# relay_and_led_RGB.net
KiCad netlist of a schematic drawn in Altium Designer
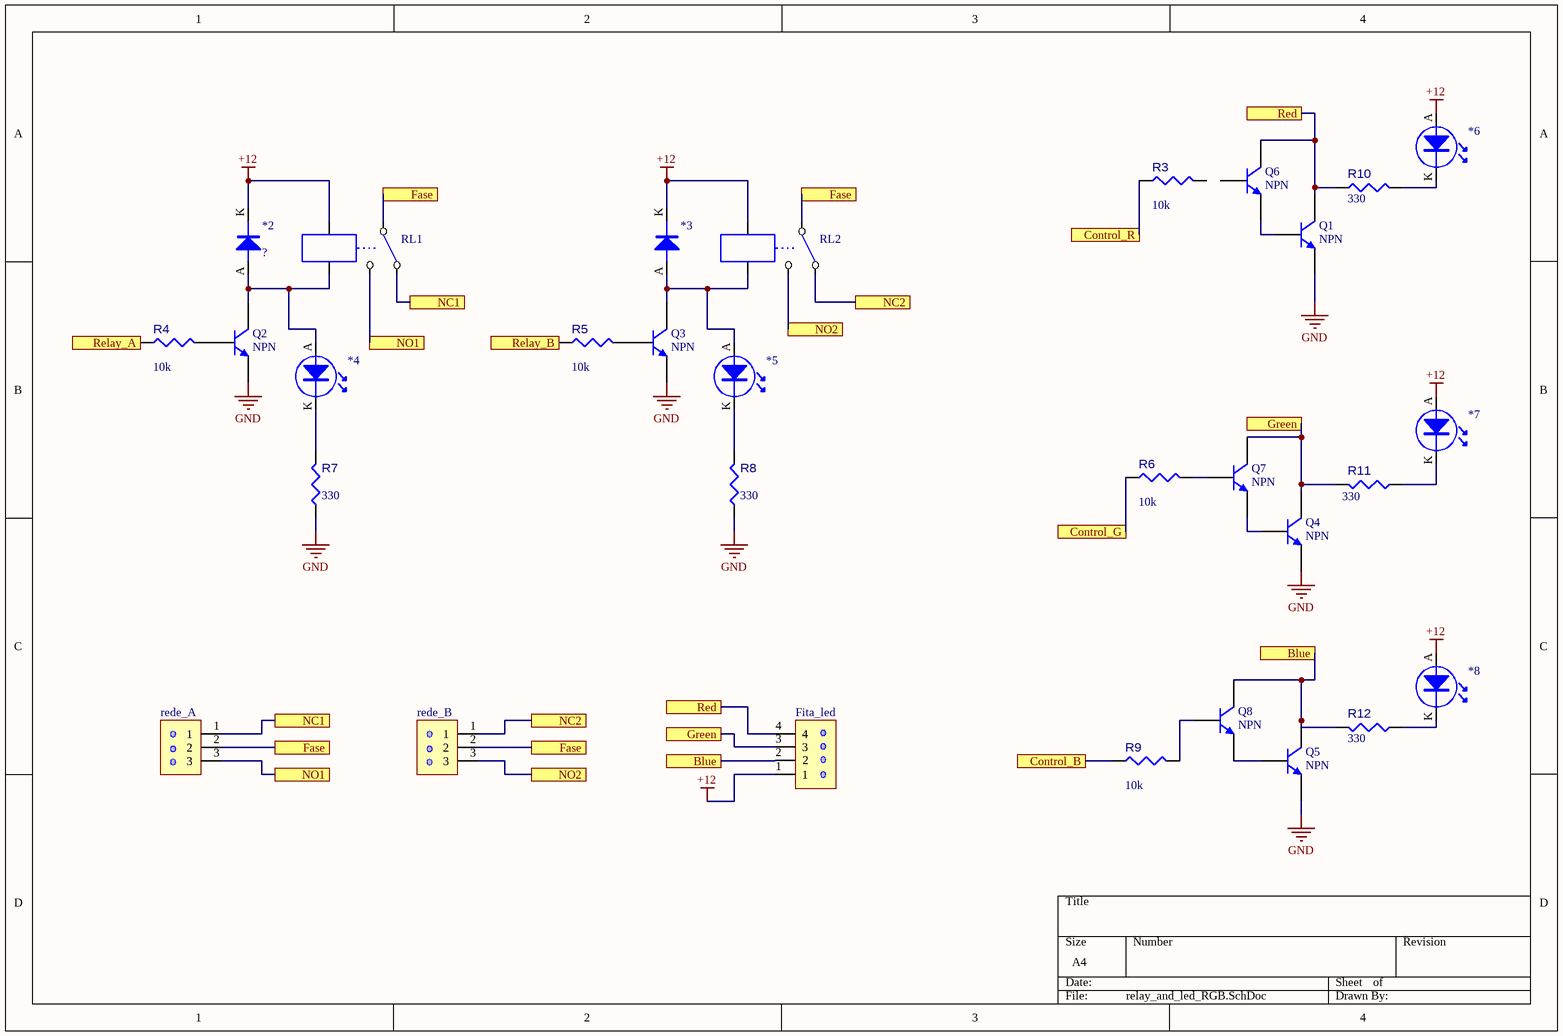
[diagram p0: relay_and_led_RGB.SchDoc]

(export (version "E")
  (design (tool "Eeschema 10.0.6"))
  (components
    (comp (ref "*2")
      (value "?")
      (footprint "DIO_PTH_DO41")
      (fields (field (name "Comment") "DIO_PTH_1N4007"))
      (libsource (lib "i9Library_Altium") (part "DIO_PTH_1N4007"))
    )
    (comp (ref "*3")
      (value "DIO_PTH_1N4007")
      (footprint "DIO_PTH_DO41")
      (libsource (lib "i9Library_Altium") (part "DIO_PTH_1N4007"))
    )
    (comp (ref "*4")
      (value "LED_AXIAL_5MM")
      (footprint "HEADER_1X2")
      (libsource (lib "i9Library_Altium") (part "LED_AXIAL_5MM"))
    )
    (comp (ref "*5")
      (value "LED_AXIAL_5MM")
      (footprint "HEADER_1X2")
      (libsource (lib "i9Library_Altium") (part "LED_AXIAL_5MM"))
    )
    (comp (ref "*6")
      (value "LED_AXIAL_5MM")
      (footprint "HEADER_1X2")
      (libsource (lib "i9Library_Altium") (part "LED_AXIAL_5MM"))
    )
    (comp (ref "*7")
      (value "LED_AXIAL_5MM")
      (footprint "HEADER_1X2")
      (libsource (lib "i9Library_Altium") (part "LED_AXIAL_5MM"))
    )
    (comp (ref "*8")
      (value "LED_AXIAL_5MM")
      (footprint "HEADER_1X2")
      (libsource (lib "i9Library_Altium") (part "LED_AXIAL_5MM"))
    )
    (comp (ref "Fita_led")
      (value "CN_KK_4")
      (footprint "CN_KK_4_5045-4")
      (description "KK_4")
      (libsource (lib "i9Library_Altium") (part "CN_KK_4"))
    )
    (comp (ref "Q1")
      (value "NPN")
      (footprint "HEADER_1X3")
      (description "NPN Bipolar Transistor")
      (fields (field (name "PUBLISHER") "Altium Limited"))
      (libsource (lib "Miscellaneous Devices") (part "NPN"))
    )
    (comp (ref "Q2")
      (value "NPN")
      (footprint "HEADER_1X3")
      (description "NPN Bipolar Transistor")
      (fields (field (name "PUBLISHER") "Altium Limited"))
      (libsource (lib "Miscellaneous Devices") (part "NPN"))
    )
    (comp (ref "Q3")
      (value "NPN")
      (footprint "HEADER_1X3")
      (description "NPN Bipolar Transistor")
      (fields (field (name "PUBLISHER") "Altium Limited"))
      (libsource (lib "Miscellaneous Devices") (part "NPN"))
    )
    (comp (ref "Q4")
      (value "NPN")
      (footprint "HEADER_1X3")
      (description "NPN Bipolar Transistor")
      (fields (field (name "PUBLISHER") "Altium Limited"))
      (libsource (lib "Miscellaneous Devices") (part "NPN"))
    )
    (comp (ref "Q5")
      (value "NPN")
      (footprint "HEADER_1X3")
      (description "NPN Bipolar Transistor")
      (fields (field (name "PUBLISHER") "Altium Limited"))
      (libsource (lib "Miscellaneous Devices") (part "NPN"))
    )
    (comp (ref "Q6")
      (value "NPN")
      (footprint "HEADER_1X3")
      (description "NPN Bipolar Transistor")
      (fields (field (name "PUBLISHER") "Altium Limited"))
      (libsource (lib "Miscellaneous Devices") (part "NPN"))
    )
    (comp (ref "Q7")
      (value "NPN")
      (footprint "HEADER_1X3")
      (description "NPN Bipolar Transistor")
      (fields (field (name "PUBLISHER") "Altium Limited"))
      (libsource (lib "Miscellaneous Devices") (part "NPN"))
    )
    (comp (ref "Q8")
      (value "NPN")
      (footprint "HEADER_1X3")
      (description "NPN Bipolar Transistor")
      (fields (field (name "PUBLISHER") "Altium Limited"))
      (libsource (lib "Miscellaneous Devices") (part "NPN"))
    )
    (comp (ref "R3")
      (value "10k")
      (footprint "RES_PTH_7.62MM")
      (description "Pin Through Hole Resistor 7.62mm")
      (libsource (lib "i9Library_Altium") (part "RES_PTH_7.62MM"))
    )
    (comp (ref "R4")
      (value "10k")
      (footprint "RES_PTH_7.62MM")
      (description "Pin Through Hole Resistor 7.62mm")
      (libsource (lib "i9Library_Altium") (part "RES_PTH_7.62MM"))
    )
    (comp (ref "R5")
      (value "10k")
      (footprint "RES_PTH_7.62MM")
      (description "Pin Through Hole Resistor 7.62mm")
      (libsource (lib "i9Library_Altium") (part "RES_PTH_7.62MM"))
    )
    (comp (ref "R6")
      (value "10k")
      (footprint "RES_PTH_7.62MM")
      (description "Pin Through Hole Resistor 7.62mm")
      (libsource (lib "i9Library_Altium") (part "RES_PTH_7.62MM"))
    )
    (comp (ref "R7")
      (value "330")
      (footprint "RES_PTH_7.62MM")
      (description "Pin Through Hole Resistor 7.62mm")
      (libsource (lib "i9Library_Altium") (part "RES_PTH_7.62MM"))
    )
    (comp (ref "R8")
      (value "330")
      (footprint "RES_PTH_7.62MM")
      (description "Pin Through Hole Resistor 7.62mm")
      (libsource (lib "i9Library_Altium") (part "RES_PTH_7.62MM"))
    )
    (comp (ref "R9")
      (value "10k")
      (footprint "RES_PTH_7.62MM")
      (description "Pin Through Hole Resistor 7.62mm")
      (libsource (lib "i9Library_Altium") (part "RES_PTH_7.62MM"))
    )
    (comp (ref "R10")
      (value "330")
      (footprint "RES_PTH_7.62MM")
      (description "Pin Through Hole Resistor 7.62mm")
      (libsource (lib "i9Library_Altium") (part "RES_PTH_7.62MM"))
    )
    (comp (ref "R11")
      (value "330")
      (footprint "RES_PTH_7.62MM")
      (description "Pin Through Hole Resistor 7.62mm")
      (libsource (lib "i9Library_Altium") (part "RES_PTH_7.62MM"))
    )
    (comp (ref "R12")
      (value "330")
      (footprint "RES_PTH_7.62MM")
      (description "Pin Through Hole Resistor 7.62mm")
      (libsource (lib "i9Library_Altium") (part "RES_PTH_7.62MM"))
    )
    (comp (ref "rede_A")
      (value "?")
      (footprint "CN_KRE_3")
      (description "MKDS_3")
      (libsource (lib "i9Library_Altium") (part "CN_MKDS_3"))
    )
    (comp (ref "rede_B")
      (value "?")
      (footprint "CN_KRE_3")
      (description "MKDS_3")
      (libsource (lib "i9Library_Altium") (part "CN_MKDS_3"))
    )
    (comp (ref "RL1")
      (value "RELEICR5551")
      (footprint "DIV_RELE_5551")
      (libsource (lib "i9Library_Altium") (part "RELEICR5551"))
    )
    (comp (ref "RL2")
      (value "RELEICR5551")
      (footprint "DIV_RELE_5551")
      (libsource (lib "i9Library_Altium") (part "RELEICR5551"))
    )
  )
  (nets
    (net (code "1") (name "+12") (class "Default")
      (node (ref "*2") (pin "K") (pintype "passive"))
      (node (ref "*3") (pin "K") (pintype "passive"))
      (node (ref "*6") (pin "A") (pintype "passive"))
      (node (ref "*7") (pin "A") (pintype "passive"))
      (node (ref "*8") (pin "A") (pintype "passive"))
      (node (ref "Fita_led") (pin "1") (pinfunction "1_1") (pintype "passive"))
      (node (ref "RL1") (pin "4") (pintype "passive"))
      (node (ref "RL2") (pin "4") (pintype "passive"))
    )
    (net (code "2") (name "/Blue") (class "Default")
      (node (ref "Fita_led") (pin "2") (pinfunction "2_2") (pintype "passive"))
      (node (ref "Q5") (pin "1") (pinfunction "C_1") (pintype "passive"))
      (node (ref "Q8") (pin "1") (pinfunction "C_1") (pintype "passive"))
      (node (ref "R12") (pin "2") (pinfunction "2_2") (pintype "passive"))
    )
    (net (code "3") (name "/Control_B") (class "Default")
      (node (ref "R9") (pin "1") (pinfunction "1_1") (pintype "passive"))
    )
    (net (code "4") (name "/Control_G") (class "Default")
      (node (ref "R6") (pin "1") (pinfunction "1_1") (pintype "passive"))
    )
    (net (code "5") (name "/Control_R") (class "Default")
      (node (ref "R3") (pin "1") (pinfunction "1_1") (pintype "passive"))
    )
    (net (code "6") (name "/Fase") (class "Default")
      (node (ref "RL1") (pin "1") (pintype "passive"))
      (node (ref "RL2") (pin "1") (pintype "passive"))
      (node (ref "rede_A") (pin "2") (pinfunction "2_2") (pintype "passive"))
      (node (ref "rede_B") (pin "2") (pinfunction "2_2") (pintype "passive"))
    )
    (net (code "7") (name "/Green") (class "Default")
      (node (ref "Fita_led") (pin "3") (pinfunction "3_3") (pintype "passive"))
      (node (ref "Q4") (pin "1") (pinfunction "C_1") (pintype "passive"))
      (node (ref "Q7") (pin "1") (pinfunction "C_1") (pintype "passive"))
      (node (ref "R11") (pin "2") (pinfunction "2_2") (pintype "passive"))
    )
    (net (code "8") (name "/NC1") (class "Default")
      (node (ref "RL1") (pin "2") (pintype "passive"))
      (node (ref "rede_A") (pin "1") (pinfunction "1_1") (pintype "passive"))
    )
    (net (code "9") (name "/NC2") (class "Default")
      (node (ref "RL2") (pin "2") (pintype "passive"))
      (node (ref "rede_B") (pin "1") (pinfunction "1_1") (pintype "passive"))
    )
    (net (code "10") (name "/NO1") (class "Default")
      (node (ref "RL1") (pin "3") (pintype "passive"))
      (node (ref "rede_A") (pin "3") (pinfunction "3_3") (pintype "passive"))
    )
    (net (code "11") (name "/NO2") (class "Default")
      (node (ref "RL2") (pin "3") (pintype "passive"))
      (node (ref "rede_B") (pin "3") (pinfunction "3_3") (pintype "passive"))
    )
    (net (code "12") (name "/Red") (class "Default")
      (node (ref "Fita_led") (pin "4") (pinfunction "4_4") (pintype "passive"))
      (node (ref "Q1") (pin "1") (pinfunction "C_1") (pintype "passive"))
      (node (ref "Q6") (pin "1") (pinfunction "C_1") (pintype "passive"))
      (node (ref "R10") (pin "1") (pinfunction "1_1") (pintype "passive"))
    )
    (net (code "13") (name "/Relay_A") (class "Default")
      (node (ref "R4") (pin "1") (pinfunction "1_1") (pintype "passive"))
    )
    (net (code "14") (name "/Relay_B") (class "Default")
      (node (ref "R5") (pin "1") (pinfunction "1_1") (pintype "passive"))
    )
    (net (code "15") (name "GND") (class "Default")
      (node (ref "Q1") (pin "3") (pinfunction "E_3") (pintype "passive"))
      (node (ref "Q2") (pin "3") (pinfunction "E_3") (pintype "passive"))
      (node (ref "Q3") (pin "3") (pinfunction "E_3") (pintype "passive"))
      (node (ref "Q4") (pin "3") (pinfunction "E_3") (pintype "passive"))
      (node (ref "Q5") (pin "3") (pinfunction "E_3") (pintype "passive"))
      (node (ref "R7") (pin "1") (pinfunction "1_1") (pintype "passive"))
      (node (ref "R8") (pin "1") (pinfunction "1_1") (pintype "passive"))
    )
    (net (code "16") (name "Net-(*4-PadK)") (class "Default")
      (node (ref "*4") (pin "K") (pintype "passive"))
      (node (ref "R7") (pin "2") (pinfunction "2_2") (pintype "passive"))
    )
    (net (code "17") (name "Net-(*5-PadK)") (class "Default")
      (node (ref "*5") (pin "K") (pintype "passive"))
      (node (ref "R8") (pin "2") (pinfunction "2_2") (pintype "passive"))
    )
    (net (code "18") (name "Net-(*6-PadK)") (class "Default")
      (node (ref "*6") (pin "K") (pintype "passive"))
      (node (ref "R10") (pin "2") (pinfunction "2_2") (pintype "passive"))
    )
    (net (code "19") (name "Net-(*7-PadK)") (class "Default")
      (node (ref "*7") (pin "K") (pintype "passive"))
      (node (ref "R11") (pin "1") (pinfunction "1_1") (pintype "passive"))
    )
    (net (code "20") (name "Net-(*8-PadK)") (class "Default")
      (node (ref "*8") (pin "K") (pintype "passive"))
      (node (ref "R12") (pin "1") (pinfunction "1_1") (pintype "passive"))
    )
    (net (code "21") (name "Net-(Q1-B)") (class "Default")
      (node (ref "Q1") (pin "2") (pinfunction "B_2") (pintype "passive"))
      (node (ref "Q6") (pin "3") (pinfunction "E_3") (pintype "passive"))
    )
    (net (code "22") (name "Net-(Q2-B)") (class "Default")
      (node (ref "Q2") (pin "2") (pinfunction "B_2") (pintype "passive"))
      (node (ref "R4") (pin "2") (pinfunction "2_2") (pintype "passive"))
    )
    (net (code "23") (name "Net-(Q2-C)") (class "Default")
      (node (ref "*2") (pin "A") (pintype "passive"))
      (node (ref "*4") (pin "A") (pintype "passive"))
      (node (ref "Q2") (pin "1") (pinfunction "C_1") (pintype "passive"))
      (node (ref "RL1") (pin "5") (pintype "passive"))
    )
    (net (code "24") (name "Net-(Q3-B)") (class "Default")
      (node (ref "Q3") (pin "2") (pinfunction "B_2") (pintype "passive"))
      (node (ref "R5") (pin "2") (pinfunction "2_2") (pintype "passive"))
    )
    (net (code "25") (name "Net-(Q3-C)") (class "Default")
      (node (ref "*3") (pin "A") (pintype "passive"))
      (node (ref "*5") (pin "A") (pintype "passive"))
      (node (ref "Q3") (pin "1") (pinfunction "C_1") (pintype "passive"))
      (node (ref "RL2") (pin "5") (pintype "passive"))
    )
    (net (code "26") (name "Net-(Q4-B)") (class "Default")
      (node (ref "Q4") (pin "2") (pinfunction "B_2") (pintype "passive"))
      (node (ref "Q7") (pin "3") (pinfunction "E_3") (pintype "passive"))
    )
    (net (code "27") (name "Net-(Q5-B)") (class "Default")
      (node (ref "Q5") (pin "2") (pinfunction "B_2") (pintype "passive"))
      (node (ref "Q8") (pin "3") (pinfunction "E_3") (pintype "passive"))
    )
    (net (code "28") (name "Net-(Q7-B)") (class "Default")
      (node (ref "Q7") (pin "2") (pinfunction "B_2") (pintype "passive"))
      (node (ref "R6") (pin "2") (pinfunction "2_2") (pintype "passive"))
    )
    (net (code "29") (name "Net-(Q8-B)") (class "Default")
      (node (ref "Q8") (pin "2") (pinfunction "B_2") (pintype "passive"))
      (node (ref "R9") (pin "2") (pinfunction "2_2") (pintype "passive"))
    )
    (net (code "30") (name "unconnected-(Q6-B-Pad2)") (class "Default")
      (node (ref "Q6") (pin "2") (pinfunction "B_2") (pintype "passive"))
    )
    (net (code "31") (name "unconnected-(R3-Pad2)") (class "Default")
      (node (ref "R3") (pin "2") (pinfunction "2_2") (pintype "passive"))
    )
  )
)
